# SCH_Esp32_2023-03-19.net
KiCad netlist of a schematic drawn in EasyEDA
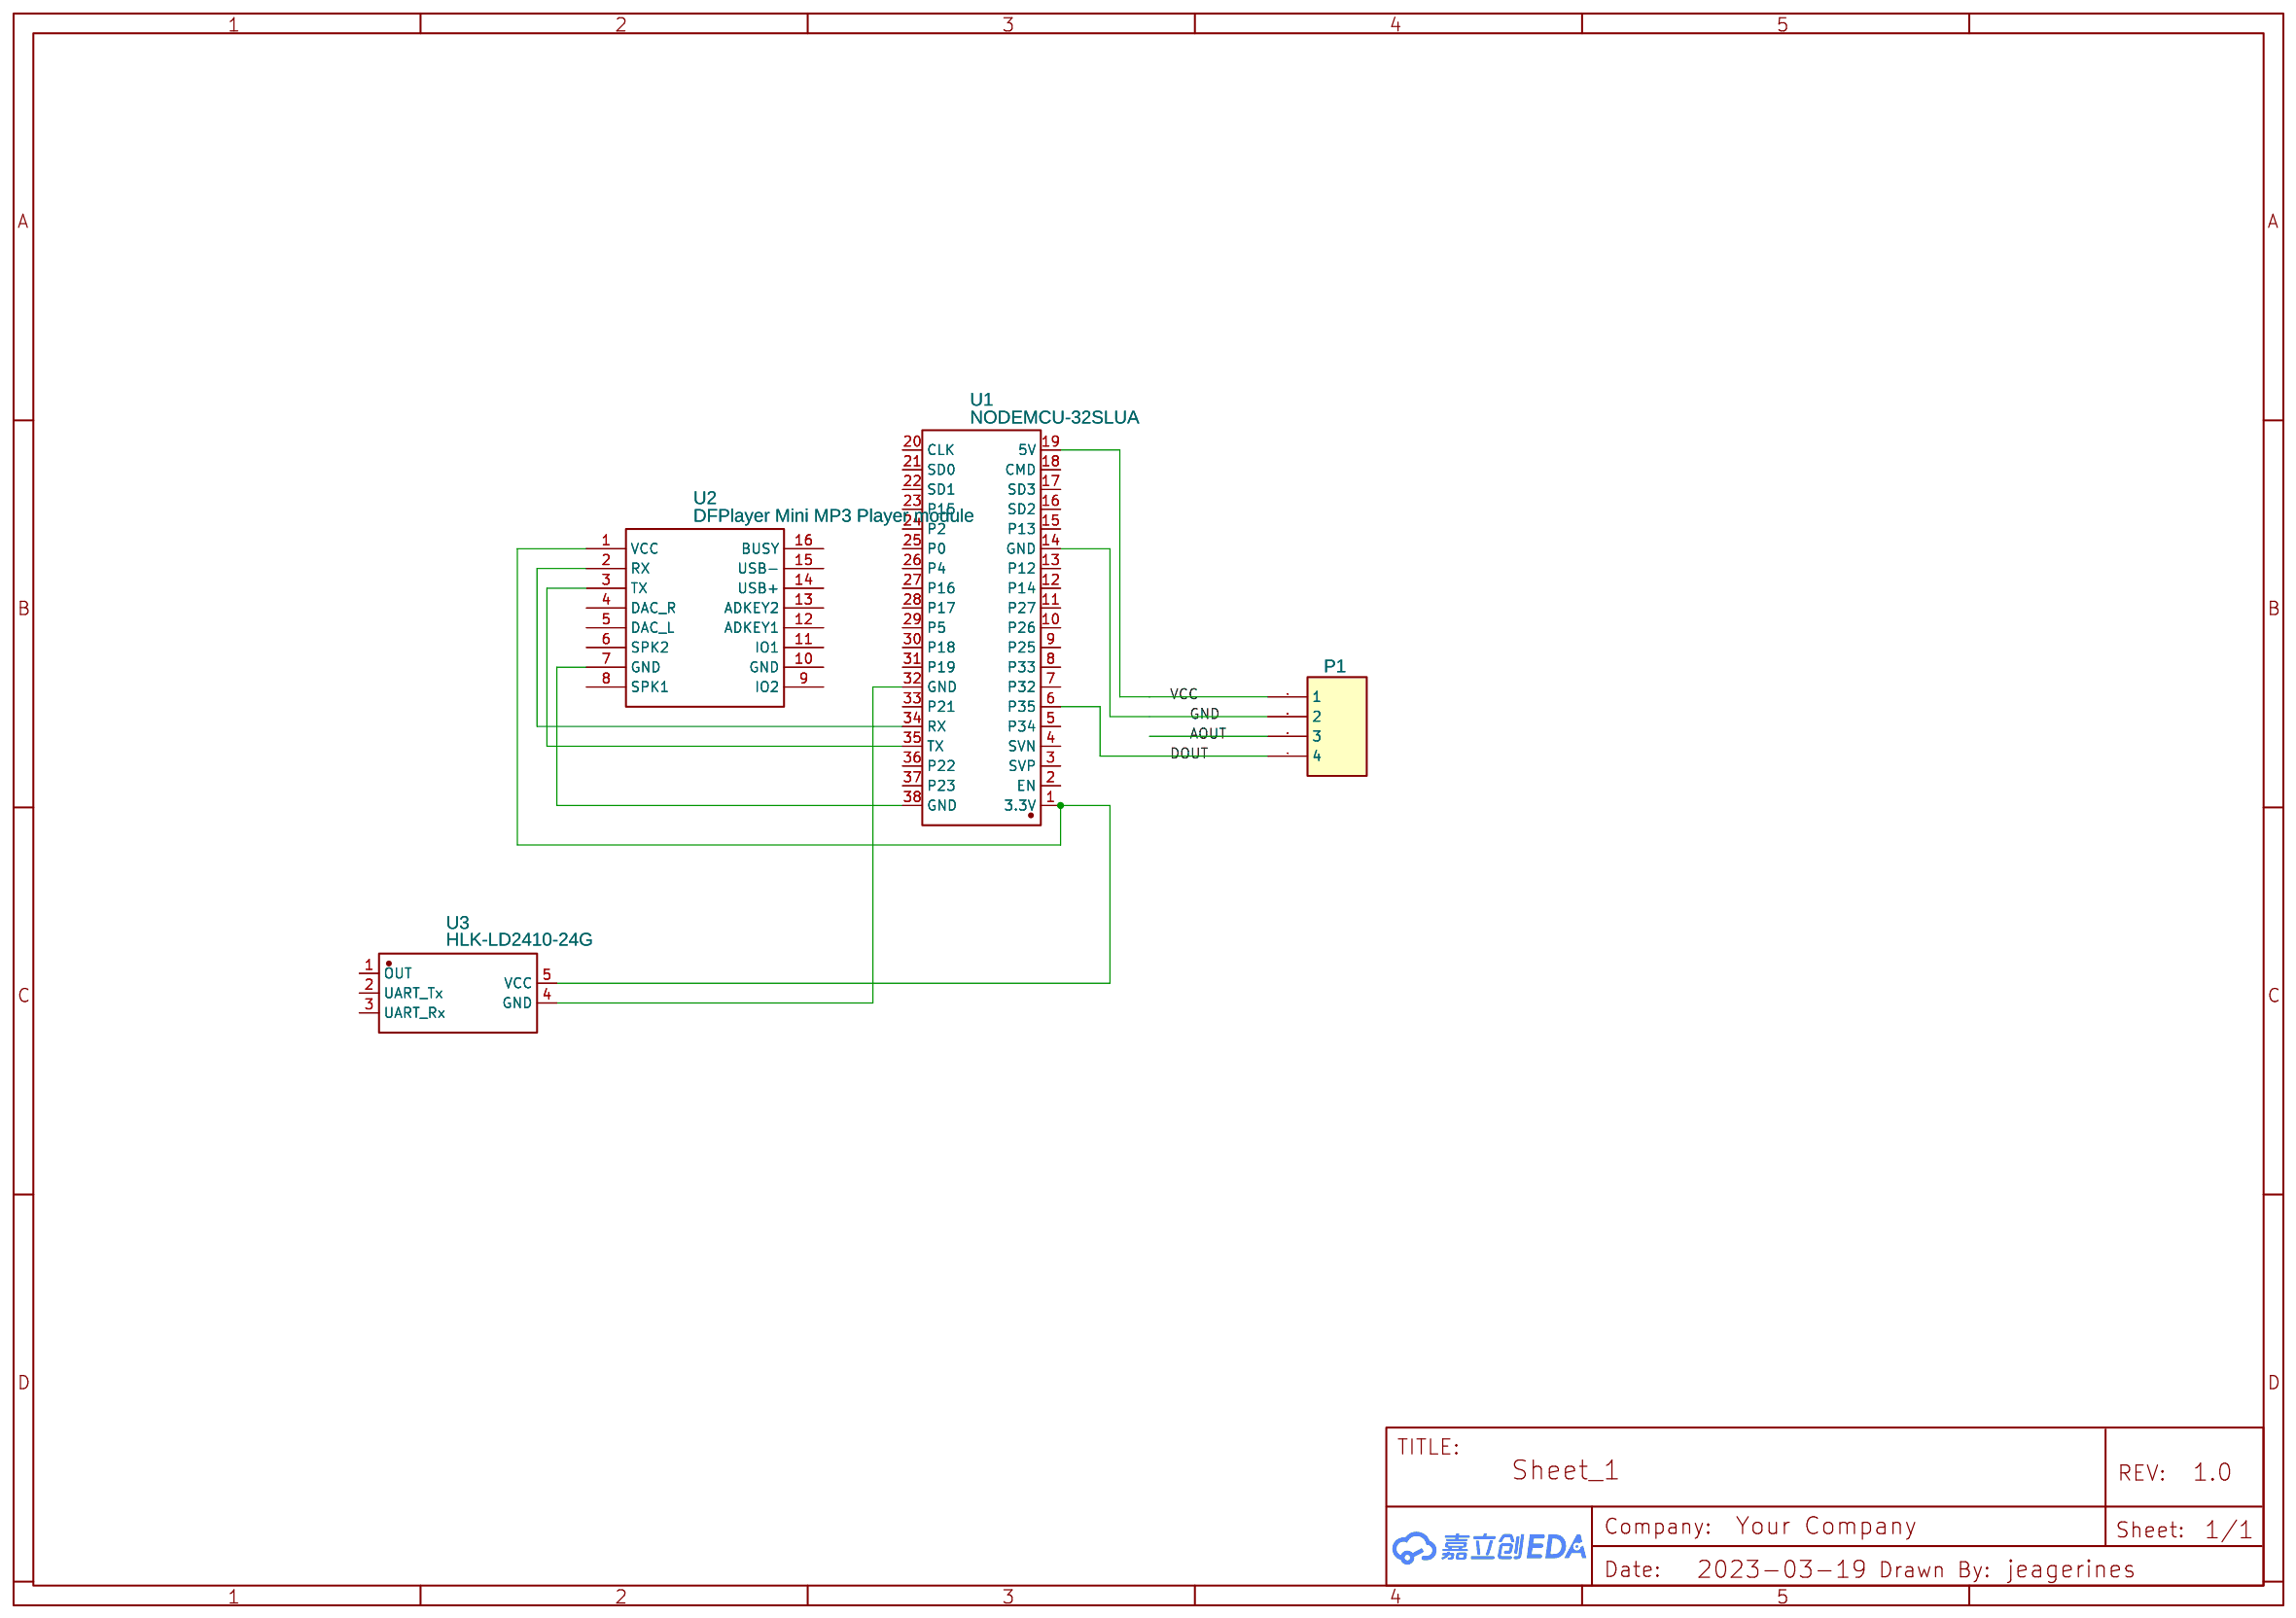
[diagram p0: schematic sheet]

(export (version "E")
  (design (tool "Eeschema 10.0.6"))
  (components
    (comp (ref "P1")
      (value "SIP4")
      (fields (field (name "BOM_Manufacturer Part") "?"))
      (libsource (lib "") (part "Unknown_655_-440"))
    )
    (comp (ref "U1")
      (value "NODEMCU-32SLUA")
      (fields
        (field (name "BOM_Manufacturer Part") "NodeMCU-32SLua")
        (field (name "BOM_Supplier Part") "C111436")
      )
      (libsource (lib "") (part "NODEMCU-32SLUA"))
    )
    (comp (ref "U2")
      (value "DFPlayer Mini MP3 Player module")
      (libsource (lib "") (part "DFPlayer Mini MP3 Player module"))
    )
    (comp (ref "U3")
      (value "HLK-LD2410-24G")
      (fields (field (name "BOM_Supplier Part") "C9900024032"))
      (libsource (lib "") (part "HLK-LD2410-24G"))
    )
  )
  (nets
    (net (code "1") (name "/AOUT") (class "Default")
      (node (ref "P1") (pin "3") (pinfunction "3_3") (pintype "unspecified"))
    )
    (net (code "2") (name "/DOUT") (class "Default")
      (node (ref "P1") (pin "4") (pinfunction "4_4") (pintype "unspecified"))
      (node (ref "U1") (pin "6") (pinfunction "P35_6") (pintype "unspecified"))
    )
    (net (code "3") (name "/GND") (class "Default")
      (node (ref "P1") (pin "2") (pinfunction "2_2") (pintype "unspecified"))
      (node (ref "U1") (pin "14") (pinfunction "GND_14") (pintype "unspecified"))
    )
    (net (code "4") (name "/VCC") (class "Default")
      (node (ref "P1") (pin "1") (pinfunction "1_1") (pintype "unspecified"))
      (node (ref "U1") (pin "19") (pinfunction "5V_19") (pintype "unspecified"))
    )
    (net (code "5") (name "Net-(U1-3.3V)") (class "Default")
      (node (ref "U1") (pin "1") (pinfunction "3.3V_1") (pintype "unspecified"))
      (node (ref "U2") (pin "1") (pinfunction "VCC_1") (pintype "unspecified"))
      (node (ref "U3") (pin "5") (pinfunction "VCC_5") (pintype "unspecified"))
    )
    (net (code "6") (name "Net-(U1-GND-Pad38)") (class "Default")
      (node (ref "U1") (pin "38") (pinfunction "GND_38") (pintype "unspecified"))
      (node (ref "U2") (pin "7") (pinfunction "GND_7") (pintype "unspecified"))
    )
    (net (code "7") (name "Net-(U1-RX)") (class "Default")
      (node (ref "U1") (pin "34") (pinfunction "RX_34") (pintype "unspecified"))
      (node (ref "U2") (pin "2") (pinfunction "RX_2") (pintype "unspecified"))
    )
    (net (code "8") (name "Net-(U1-TX)") (class "Default")
      (node (ref "U1") (pin "35") (pinfunction "TX_35") (pintype "unspecified"))
      (node (ref "U2") (pin "3") (pinfunction "TX_3") (pintype "unspecified"))
    )
    (net (code "9") (name "Net-(U3-GND)") (class "Default")
      (node (ref "U1") (pin "32") (pinfunction "GND_32") (pintype "unspecified"))
      (node (ref "U3") (pin "4") (pinfunction "GND_4") (pintype "unspecified"))
    )
    (net (code "10") (name "unconnected-(U1-CLK-Pad20)") (class "Default")
      (node (ref "U1") (pin "20") (pinfunction "CLK_20") (pintype "unspecified"))
    )
    (net (code "11") (name "unconnected-(U1-CMD-Pad18)") (class "Default")
      (node (ref "U1") (pin "18") (pinfunction "CMD_18") (pintype "unspecified"))
    )
    (net (code "12") (name "unconnected-(U1-EN-Pad2)") (class "Default")
      (node (ref "U1") (pin "2") (pinfunction "EN_2") (pintype "unspecified"))
    )
    (net (code "13") (name "unconnected-(U1-P0-Pad25)") (class "Default")
      (node (ref "U1") (pin "25") (pinfunction "P0_25") (pintype "unspecified"))
    )
    (net (code "14") (name "unconnected-(U1-P2-Pad24)") (class "Default")
      (node (ref "U1") (pin "24") (pinfunction "P2_24") (pintype "unspecified"))
    )
    (net (code "15") (name "unconnected-(U1-P4-Pad26)") (class "Default")
      (node (ref "U1") (pin "26") (pinfunction "P4_26") (pintype "unspecified"))
    )
    (net (code "16") (name "unconnected-(U1-P5-Pad29)") (class "Default")
      (node (ref "U1") (pin "29") (pinfunction "P5_29") (pintype "unspecified"))
    )
    (net (code "17") (name "unconnected-(U1-P12-Pad13)") (class "Default")
      (node (ref "U1") (pin "13") (pinfunction "P12_13") (pintype "unspecified"))
    )
    (net (code "18") (name "unconnected-(U1-P13-Pad15)") (class "Default")
      (node (ref "U1") (pin "15") (pinfunction "P13_15") (pintype "unspecified"))
    )
    (net (code "19") (name "unconnected-(U1-P14-Pad12)") (class "Default")
      (node (ref "U1") (pin "12") (pinfunction "P14_12") (pintype "unspecified"))
    )
    (net (code "20") (name "unconnected-(U1-P15-Pad23)") (class "Default")
      (node (ref "U1") (pin "23") (pinfunction "P15_23") (pintype "unspecified"))
    )
    (net (code "21") (name "unconnected-(U1-P16-Pad27)") (class "Default")
      (node (ref "U1") (pin "27") (pinfunction "P16_27") (pintype "unspecified"))
    )
    (net (code "22") (name "unconnected-(U1-P17-Pad28)") (class "Default")
      (node (ref "U1") (pin "28") (pinfunction "P17_28") (pintype "unspecified"))
    )
    (net (code "23") (name "unconnected-(U1-P18-Pad30)") (class "Default")
      (node (ref "U1") (pin "30") (pinfunction "P18_30") (pintype "unspecified"))
    )
    (net (code "24") (name "unconnected-(U1-P19-Pad31)") (class "Default")
      (node (ref "U1") (pin "31") (pinfunction "P19_31") (pintype "unspecified"))
    )
    (net (code "25") (name "unconnected-(U1-P21-Pad33)") (class "Default")
      (node (ref "U1") (pin "33") (pinfunction "P21_33") (pintype "unspecified"))
    )
    (net (code "26") (name "unconnected-(U1-P22-Pad36)") (class "Default")
      (node (ref "U1") (pin "36") (pinfunction "P22_36") (pintype "unspecified"))
    )
    (net (code "27") (name "unconnected-(U1-P23-Pad37)") (class "Default")
      (node (ref "U1") (pin "37") (pinfunction "P23_37") (pintype "unspecified"))
    )
    (net (code "28") (name "unconnected-(U1-P25-Pad9)") (class "Default")
      (node (ref "U1") (pin "9") (pinfunction "P25_9") (pintype "unspecified"))
    )
    (net (code "29") (name "unconnected-(U1-P26-Pad10)") (class "Default")
      (node (ref "U1") (pin "10") (pinfunction "P26_10") (pintype "unspecified"))
    )
    (net (code "30") (name "unconnected-(U1-P27-Pad11)") (class "Default")
      (node (ref "U1") (pin "11") (pinfunction "P27_11") (pintype "unspecified"))
    )
    (net (code "31") (name "unconnected-(U1-P32-Pad7)") (class "Default")
      (node (ref "U1") (pin "7") (pinfunction "P32_7") (pintype "unspecified"))
    )
    (net (code "32") (name "unconnected-(U1-P33-Pad8)") (class "Default")
      (node (ref "U1") (pin "8") (pinfunction "P33_8") (pintype "unspecified"))
    )
    (net (code "33") (name "unconnected-(U1-P34-Pad5)") (class "Default")
      (node (ref "U1") (pin "5") (pinfunction "P34_5") (pintype "unspecified"))
    )
    (net (code "34") (name "unconnected-(U1-SD0-Pad21)") (class "Default")
      (node (ref "U1") (pin "21") (pinfunction "SD0_21") (pintype "unspecified"))
    )
    (net (code "35") (name "unconnected-(U1-SD1-Pad22)") (class "Default")
      (node (ref "U1") (pin "22") (pinfunction "SD1_22") (pintype "unspecified"))
    )
    (net (code "36") (name "unconnected-(U1-SD2-Pad16)") (class "Default")
      (node (ref "U1") (pin "16") (pinfunction "SD2_16") (pintype "unspecified"))
    )
    (net (code "37") (name "unconnected-(U1-SD3-Pad17)") (class "Default")
      (node (ref "U1") (pin "17") (pinfunction "SD3_17") (pintype "unspecified"))
    )
    (net (code "38") (name "unconnected-(U1-SVN-Pad4)") (class "Default")
      (node (ref "U1") (pin "4") (pinfunction "SVN_4") (pintype "unspecified"))
    )
    (net (code "39") (name "unconnected-(U1-SVP-Pad3)") (class "Default")
      (node (ref "U1") (pin "3") (pinfunction "SVP_3") (pintype "unspecified"))
    )
    (net (code "40") (name "unconnected-(U2-ADKEY1-Pad12)") (class "Default")
      (node (ref "U2") (pin "12") (pinfunction "ADKEY1_12") (pintype "unspecified"))
    )
    (net (code "41") (name "unconnected-(U2-ADKEY2-Pad13)") (class "Default")
      (node (ref "U2") (pin "13") (pinfunction "ADKEY2_13") (pintype "unspecified"))
    )
    (net (code "42") (name "unconnected-(U2-BUSY-Pad16)") (class "Default")
      (node (ref "U2") (pin "16") (pinfunction "BUSY_16") (pintype "unspecified"))
    )
    (net (code "43") (name "unconnected-(U2-DAC_L-Pad5)") (class "Default")
      (node (ref "U2") (pin "5") (pinfunction "DAC_L_5") (pintype "unspecified"))
    )
    (net (code "44") (name "unconnected-(U2-DAC_R-Pad4)") (class "Default")
      (node (ref "U2") (pin "4") (pinfunction "DAC_R_4") (pintype "unspecified"))
    )
    (net (code "45") (name "unconnected-(U2-GND-Pad10)") (class "Default")
      (node (ref "U2") (pin "10") (pinfunction "GND_10") (pintype "unspecified"))
    )
    (net (code "46") (name "unconnected-(U2-IO1-Pad11)") (class "Default")
      (node (ref "U2") (pin "11") (pinfunction "IO1_11") (pintype "unspecified"))
    )
    (net (code "47") (name "unconnected-(U2-IO2-Pad9)") (class "Default")
      (node (ref "U2") (pin "9") (pinfunction "IO2_9") (pintype "unspecified"))
    )
    (net (code "48") (name "unconnected-(U2-SPK1-Pad8)") (class "Default")
      (node (ref "U2") (pin "8") (pinfunction "SPK1_8") (pintype "unspecified"))
    )
    (net (code "49") (name "unconnected-(U2-SPK2-Pad6)") (class "Default")
      (node (ref "U2") (pin "6") (pinfunction "SPK2_6") (pintype "unspecified"))
    )
    (net (code "50") (name "unconnected-(U2-USB+-Pad14)") (class "Default")
      (node (ref "U2") (pin "14") (pinfunction "USB+_14") (pintype "unspecified"))
    )
    (net (code "51") (name "unconnected-(U2-USB--Pad15)") (class "Default")
      (node (ref "U2") (pin "15") (pinfunction "USB-_15") (pintype "unspecified"))
    )
    (net (code "52") (name "unconnected-(U3-OUT-Pad1)") (class "Default")
      (node (ref "U3") (pin "1") (pinfunction "OUT_1") (pintype "unspecified"))
    )
    (net (code "53") (name "unconnected-(U3-UART_Rx-Pad3)") (class "Default")
      (node (ref "U3") (pin "3") (pinfunction "UART_Rx_3") (pintype "unspecified"))
    )
    (net (code "54") (name "unconnected-(U3-UART_Tx-Pad2)") (class "Default")
      (node (ref "U3") (pin "2") (pinfunction "UART_Tx_2") (pintype "unspecified"))
    )
  )
)
